# schematic.net
KiCad netlist of a schematic drawn in EAGLE
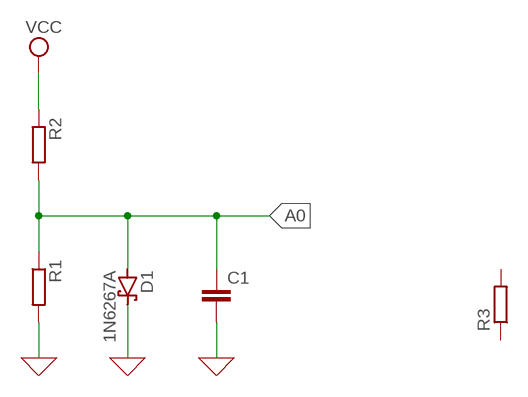
[diagram p0: schematic, sheet 1]

(export (version "E")
  (design (tool "Eeschema 10.0.6"))
  (components
    (comp (ref "C1")
      (value "C-EU025-025X050")
      (footprint "eagle-import:C025-025X050")
      (libsource (lib "eagle-import") (part "C-EU025-025X050"))
    )
    (comp (ref "D1")
      (value "1N6267A")
      (footprint "eagle-import:C4111-15")
      (libsource (lib "eagle-import") (part "1N6267A"))
    )
    (comp (ref "R1")
      (value "R-EU_0204/7")
      (footprint "eagle-import:0204_7")
      (libsource (lib "eagle-import") (part "R-EU_0204/7"))
    )
    (comp (ref "R2")
      (value "R-EU_0204/7")
      (footprint "eagle-import:0204_7")
      (libsource (lib "eagle-import") (part "R-EU_0204/7"))
    )
    (comp (ref "R3")
      (value "R-EU_0204/7")
      (footprint "eagle-import:0204_7")
      (libsource (lib "eagle-import") (part "R-EU_0204/7"))
    )
  )
  (nets
    (net (code "1") (name "A0") (class "Default")
      (node (ref "C1") (pin "1") (pinfunction "1_1") (pintype "passive"))
      (node (ref "D1") (pin "A") (pinfunction "A_A") (pintype "passive"))
      (node (ref "R1") (pin "1") (pinfunction "1_1") (pintype "passive"))
      (node (ref "R2") (pin "2") (pinfunction "2_2") (pintype "passive"))
    )
    (net (code "2") (name "GND") (class "Default")
      (node (ref "C1") (pin "2") (pinfunction "2_2") (pintype "passive"))
      (node (ref "D1") (pin "C") (pinfunction "C_C") (pintype "passive"))
      (node (ref "R1") (pin "2") (pinfunction "2_2") (pintype "passive"))
    )
    (net (code "3") (name "VCC") (class "Default")
      (node (ref "R2") (pin "1") (pinfunction "1_1") (pintype "passive"))
    )
    (net (code "4") (name "unconnected-(R3-Pad1)") (class "Default")
      (node (ref "R3") (pin "1") (pinfunction "1_1") (pintype "passive"))
    )
    (net (code "5") (name "unconnected-(R3-Pad2)") (class "Default")
      (node (ref "R3") (pin "2") (pinfunction "2_2") (pintype "passive"))
    )
  )
)
